# pecl_pulse_driver.net
KiCad netlist of a schematic drawn in EAGLE
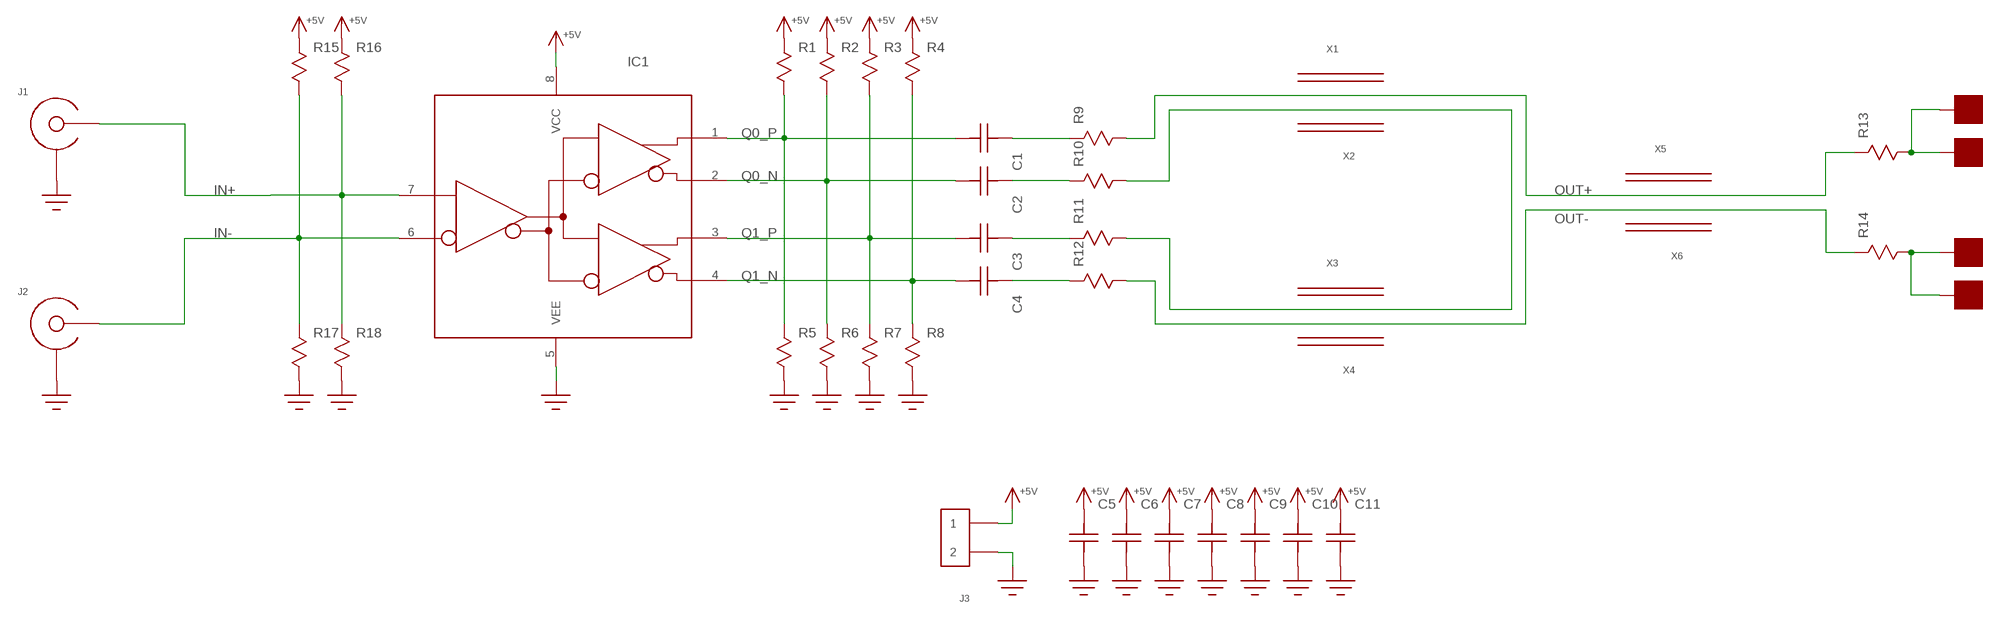
[diagram p0: schematic, sheet 1]

(export (version "E")
  (design (tool "Eeschema 10.0.6"))
  (components
    (comp (ref "C1")
      (value "C0603")
      (footprint "eagle-import:C0603")
      (libsource (lib "eagle-import") (part "C0603"))
    )
    (comp (ref "C2")
      (value "C0603")
      (footprint "eagle-import:C0603")
      (libsource (lib "eagle-import") (part "C0603"))
    )
    (comp (ref "C3")
      (value "C0603")
      (footprint "eagle-import:C0603")
      (libsource (lib "eagle-import") (part "C0603"))
    )
    (comp (ref "C4")
      (value "C0603")
      (footprint "eagle-import:C0603")
      (libsource (lib "eagle-import") (part "C0603"))
    )
    (comp (ref "C5")
      (value "C0603")
      (footprint "eagle-import:C0603")
      (libsource (lib "eagle-import") (part "C0603"))
    )
    (comp (ref "C6")
      (value "C0603")
      (footprint "eagle-import:C0603")
      (libsource (lib "eagle-import") (part "C0603"))
    )
    (comp (ref "C7")
      (value "C0805")
      (footprint "eagle-import:0805")
      (libsource (lib "eagle-import") (part "C0805"))
    )
    (comp (ref "C8")
      (value "C0603")
      (footprint "eagle-import:C0603")
      (libsource (lib "eagle-import") (part "C0603"))
    )
    (comp (ref "C9")
      (value "C0603")
      (footprint "eagle-import:C0603")
      (libsource (lib "eagle-import") (part "C0603"))
    )
    (comp (ref "C10")
      (value "C0603")
      (footprint "eagle-import:C0603")
      (libsource (lib "eagle-import") (part "C0603"))
    )
    (comp (ref "C11")
      (value "C0603")
      (footprint "eagle-import:C0603")
      (libsource (lib "eagle-import") (part "C0603"))
    )
    (comp (ref "IC1")
      (value "SY10EP89V")
      (footprint "eagle-import:SOIC8")
      (libsource (lib "eagle-import") (part "SY10EP89V"))
    )
    (comp (ref "J1")
      (value "EDGE_LAUNCH_JACK")
      (footprint "eagle-import:EDGE_LAUNCH_RF_CON")
      (libsource (lib "eagle-import") (part "EDGE_LAUNCH_JACK"))
    )
    (comp (ref "J2")
      (value "EDGE_LAUNCH_JACK")
      (footprint "eagle-import:EDGE_LAUNCH_RF_CON")
      (libsource (lib "eagle-import") (part "EDGE_LAUNCH_JACK"))
    )
    (comp (ref "J3")
      (value "HEADER_2PIN")
      (footprint "eagle-import:HEADER_2PIN")
      (libsource (lib "eagle-import") (part "HEADER_2PIN"))
    )
    (comp (ref "R1")
      (value "R0603")
      (footprint "eagle-import:R0603")
      (libsource (lib "eagle-import") (part "R0603"))
    )
    (comp (ref "R2")
      (value "R0603")
      (footprint "eagle-import:R0603")
      (libsource (lib "eagle-import") (part "R0603"))
    )
    (comp (ref "R3")
      (value "R0603")
      (footprint "eagle-import:R0603")
      (libsource (lib "eagle-import") (part "R0603"))
    )
    (comp (ref "R4")
      (value "R0603")
      (footprint "eagle-import:R0603")
      (libsource (lib "eagle-import") (part "R0603"))
    )
    (comp (ref "R5")
      (value "R0603")
      (footprint "eagle-import:R0603")
      (libsource (lib "eagle-import") (part "R0603"))
    )
    (comp (ref "R6")
      (value "R0603")
      (footprint "eagle-import:R0603")
      (libsource (lib "eagle-import") (part "R0603"))
    )
    (comp (ref "R7")
      (value "R0603")
      (footprint "eagle-import:R0603")
      (libsource (lib "eagle-import") (part "R0603"))
    )
    (comp (ref "R8")
      (value "R0603")
      (footprint "eagle-import:R0603")
      (libsource (lib "eagle-import") (part "R0603"))
    )
    (comp (ref "R9")
      (value "R0603")
      (footprint "eagle-import:R0603")
      (libsource (lib "eagle-import") (part "R0603"))
    )
    (comp (ref "R10")
      (value "R0603")
      (footprint "eagle-import:R0603")
      (libsource (lib "eagle-import") (part "R0603"))
    )
    (comp (ref "R11")
      (value "R0603")
      (footprint "eagle-import:R0603")
      (libsource (lib "eagle-import") (part "R0603"))
    )
    (comp (ref "R12")
      (value "R0603")
      (footprint "eagle-import:R0603")
      (libsource (lib "eagle-import") (part "R0603"))
    )
    (comp (ref "R13")
      (value "R0603")
      (footprint "eagle-import:R0603")
      (libsource (lib "eagle-import") (part "R0603"))
    )
    (comp (ref "R14")
      (value "R0603")
      (footprint "eagle-import:R0603")
      (libsource (lib "eagle-import") (part "R0603"))
    )
    (comp (ref "R15")
      (value "R0603")
      (footprint "eagle-import:R0603")
      (libsource (lib "eagle-import") (part "R0603"))
    )
    (comp (ref "R16")
      (value "R0603")
      (footprint "eagle-import:R0603")
      (libsource (lib "eagle-import") (part "R0603"))
    )
    (comp (ref "R17")
      (value "R0603")
      (footprint "eagle-import:R0603")
      (libsource (lib "eagle-import") (part "R0603"))
    )
    (comp (ref "R18")
      (value "R0603")
      (footprint "eagle-import:R0603")
      (libsource (lib "eagle-import") (part "R0603"))
    )
    (comp (ref "U$4")
      (value "PAD50MIL")
      (footprint "eagle-import:PAD_50MIL")
      (libsource (lib "eagle-import") (part "PAD50MIL"))
    )
    (comp (ref "U$5")
      (value "PAD50MIL")
      (footprint "eagle-import:PAD_50MIL")
      (libsource (lib "eagle-import") (part "PAD50MIL"))
    )
    (comp (ref "U$35")
      (value "PAD50MIL")
      (footprint "eagle-import:PAD_50MIL")
      (libsource (lib "eagle-import") (part "PAD50MIL"))
    )
    (comp (ref "U$36")
      (value "PAD50MIL")
      (footprint "eagle-import:PAD_50MIL")
      (libsource (lib "eagle-import") (part "PAD50MIL"))
    )
    (comp (ref "X1")
      (value "FERRITE_PLATE")
      (footprint "eagle-import:FERRITE-MP0350")
      (libsource (lib "eagle-import") (part "FERRITE_PLATE"))
    )
    (comp (ref "X2")
      (value "FERRITE_PLATE")
      (footprint "eagle-import:FERRITE-MP0350")
      (libsource (lib "eagle-import") (part "FERRITE_PLATE"))
    )
    (comp (ref "X3")
      (value "FERRITE_PLATE")
      (footprint "eagle-import:FERRITE-MP0350")
      (libsource (lib "eagle-import") (part "FERRITE_PLATE"))
    )
    (comp (ref "X4")
      (value "FERRITE_PLATE")
      (footprint "eagle-import:FERRITE-MP0350")
      (libsource (lib "eagle-import") (part "FERRITE_PLATE"))
    )
    (comp (ref "X5")
      (value "FERRITE_PLATE")
      (footprint "eagle-import:FERRITE-MP0350")
      (libsource (lib "eagle-import") (part "FERRITE_PLATE"))
    )
    (comp (ref "X6")
      (value "FERRITE_PLATE")
      (footprint "eagle-import:FERRITE-MP0350")
      (libsource (lib "eagle-import") (part "FERRITE_PLATE"))
    )
  )
  (nets
    (net (code "1") (name "+5V") (class "Default")
      (node (ref "C10") (pin "P$2") (pinfunction "P$2_P$2") (pintype "bidirectional"))
      (node (ref "C11") (pin "P$2") (pinfunction "P$2_P$2") (pintype "bidirectional"))
      (node (ref "C5") (pin "P$2") (pinfunction "P$2_P$2") (pintype "bidirectional"))
      (node (ref "C6") (pin "P$2") (pinfunction "P$2_P$2") (pintype "bidirectional"))
      (node (ref "C7") (pin "P$2") (pinfunction "P$2_P$2") (pintype "bidirectional"))
      (node (ref "C8") (pin "P$2") (pinfunction "P$2_P$2") (pintype "bidirectional"))
      (node (ref "C9") (pin "P$2") (pinfunction "P$2_P$2") (pintype "bidirectional"))
      (node (ref "IC1") (pin "8") (pinfunction "VCC_8") (pintype "bidirectional"))
      (node (ref "J3") (pin "1") (pinfunction "1_1") (pintype "bidirectional"))
      (node (ref "R1") (pin "P$1") (pinfunction "P$3_P$1") (pintype "bidirectional"))
      (node (ref "R15") (pin "P$1") (pinfunction "P$3_P$1") (pintype "bidirectional"))
      (node (ref "R16") (pin "P$1") (pinfunction "P$3_P$1") (pintype "bidirectional"))
      (node (ref "R2") (pin "P$1") (pinfunction "P$3_P$1") (pintype "bidirectional"))
      (node (ref "R3") (pin "P$1") (pinfunction "P$3_P$1") (pintype "bidirectional"))
      (node (ref "R4") (pin "P$1") (pinfunction "P$3_P$1") (pintype "bidirectional"))
    )
    (net (code "2") (name "/IN+") (class "Default")
      (node (ref "IC1") (pin "7") (pinfunction "D_7") (pintype "bidirectional"))
      (node (ref "J1") (pin "CENTER") (pinfunction "CENTER_CENTER") (pintype "bidirectional"))
      (node (ref "R16") (pin "P$2") (pinfunction "P$4_P$2") (pintype "bidirectional"))
      (node (ref "R18") (pin "P$1") (pinfunction "P$3_P$1") (pintype "bidirectional"))
    )
    (net (code "3") (name "/IN-") (class "Default")
      (node (ref "IC1") (pin "6") (pinfunction "~{D}_6") (pintype "bidirectional"))
      (node (ref "J2") (pin "CENTER") (pinfunction "CENTER_CENTER") (pintype "bidirectional"))
      (node (ref "R15") (pin "P$2") (pinfunction "P$4_P$2") (pintype "bidirectional"))
      (node (ref "R17") (pin "P$1") (pinfunction "P$3_P$1") (pintype "bidirectional"))
    )
    (net (code "4") (name "/OUT+") (class "Default")
      (node (ref "R13") (pin "P$1") (pinfunction "P$3_P$1") (pintype "bidirectional"))
      (node (ref "R9") (pin "P$2") (pinfunction "P$4_P$2") (pintype "bidirectional"))
    )
    (net (code "5") (name "/OUT-") (class "Default")
      (node (ref "R12") (pin "P$2") (pinfunction "P$4_P$2") (pintype "bidirectional"))
      (node (ref "R14") (pin "P$1") (pinfunction "P$3_P$1") (pintype "bidirectional"))
    )
    (net (code "6") (name "/Q0_N") (class "Default")
      (node (ref "C2") (pin "P$1") (pinfunction "P$1_P$1") (pintype "bidirectional"))
      (node (ref "IC1") (pin "2") (pinfunction "~{Q0}_2") (pintype "bidirectional"))
      (node (ref "R2") (pin "P$2") (pinfunction "P$4_P$2") (pintype "bidirectional"))
      (node (ref "R6") (pin "P$1") (pinfunction "P$3_P$1") (pintype "bidirectional"))
    )
    (net (code "7") (name "/Q0_P") (class "Default")
      (node (ref "C1") (pin "P$1") (pinfunction "P$1_P$1") (pintype "bidirectional"))
      (node (ref "IC1") (pin "1") (pinfunction "Q0_1") (pintype "bidirectional"))
      (node (ref "R1") (pin "P$2") (pinfunction "P$4_P$2") (pintype "bidirectional"))
      (node (ref "R5") (pin "P$1") (pinfunction "P$3_P$1") (pintype "bidirectional"))
    )
    (net (code "8") (name "/Q1_N") (class "Default")
      (node (ref "C4") (pin "P$1") (pinfunction "P$1_P$1") (pintype "bidirectional"))
      (node (ref "IC1") (pin "4") (pinfunction "~{Q1}_4") (pintype "bidirectional"))
      (node (ref "R4") (pin "P$2") (pinfunction "P$4_P$2") (pintype "bidirectional"))
      (node (ref "R8") (pin "P$1") (pinfunction "P$3_P$1") (pintype "bidirectional"))
    )
    (net (code "9") (name "/Q1_P") (class "Default")
      (node (ref "C3") (pin "P$1") (pinfunction "P$1_P$1") (pintype "bidirectional"))
      (node (ref "IC1") (pin "3") (pinfunction "Q1_3") (pintype "bidirectional"))
      (node (ref "R3") (pin "P$2") (pinfunction "P$4_P$2") (pintype "bidirectional"))
      (node (ref "R7") (pin "P$1") (pinfunction "P$3_P$1") (pintype "bidirectional"))
    )
    (net (code "10") (name "GND") (class "Default")
      (node (ref "C10") (pin "P$1") (pinfunction "P$1_P$1") (pintype "bidirectional"))
      (node (ref "C11") (pin "P$1") (pinfunction "P$1_P$1") (pintype "bidirectional"))
      (node (ref "C5") (pin "P$1") (pinfunction "P$1_P$1") (pintype "bidirectional"))
      (node (ref "C6") (pin "P$1") (pinfunction "P$1_P$1") (pintype "bidirectional"))
      (node (ref "C7") (pin "P$1") (pinfunction "P$1_P$1") (pintype "bidirectional"))
      (node (ref "C8") (pin "P$1") (pinfunction "P$1_P$1") (pintype "bidirectional"))
      (node (ref "C9") (pin "P$1") (pinfunction "P$1_P$1") (pintype "bidirectional"))
      (node (ref "IC1") (pin "5") (pinfunction "VEE_5") (pintype "bidirectional"))
      (node (ref "J1") (pin "GND@1") (pinfunction "SHIELD_GND@1") (pintype "bidirectional"))
      (node (ref "J1") (pin "GND@10") (pinfunction "SHIELD_GND@10") (pintype "bidirectional"))
      (node (ref "J1") (pin "GND@11") (pinfunction "SHIELD_GND@11") (pintype "bidirectional"))
      (node (ref "J1") (pin "GND@12") (pinfunction "SHIELD_GND@12") (pintype "bidirectional"))
      (node (ref "J1") (pin "GND@2") (pinfunction "SHIELD_GND@2") (pintype "bidirectional"))
      (node (ref "J1") (pin "GND@3") (pinfunction "SHIELD_GND@3") (pintype "bidirectional"))
      (node (ref "J1") (pin "GND@4") (pinfunction "SHIELD_GND@4") (pintype "bidirectional"))
      (node (ref "J1") (pin "GND@5") (pinfunction "SHIELD_GND@5") (pintype "bidirectional"))
      (node (ref "J1") (pin "GND@6") (pinfunction "SHIELD_GND@6") (pintype "bidirectional"))
      (node (ref "J1") (pin "GND@7") (pinfunction "SHIELD_GND@7") (pintype "bidirectional"))
      (node (ref "J1") (pin "GND@8") (pinfunction "SHIELD_GND@8") (pintype "bidirectional"))
      (node (ref "J1") (pin "GND@9") (pinfunction "SHIELD_GND@9") (pintype "bidirectional"))
      (node (ref "J1") (pin "SHIELD@1") (pinfunction "SHIELD_SHIELD@1") (pintype "bidirectional"))
      (node (ref "J1") (pin "SHIELD@2") (pinfunction "SHIELD_SHIELD@2") (pintype "bidirectional"))
      (node (ref "J2") (pin "GND@1") (pinfunction "SHIELD_GND@1") (pintype "bidirectional"))
      (node (ref "J2") (pin "GND@10") (pinfunction "SHIELD_GND@10") (pintype "bidirectional"))
      (node (ref "J2") (pin "GND@11") (pinfunction "SHIELD_GND@11") (pintype "bidirectional"))
      (node (ref "J2") (pin "GND@12") (pinfunction "SHIELD_GND@12") (pintype "bidirectional"))
      (node (ref "J2") (pin "GND@2") (pinfunction "SHIELD_GND@2") (pintype "bidirectional"))
      (node (ref "J2") (pin "GND@3") (pinfunction "SHIELD_GND@3") (pintype "bidirectional"))
      (node (ref "J2") (pin "GND@4") (pinfunction "SHIELD_GND@4") (pintype "bidirectional"))
      (node (ref "J2") (pin "GND@5") (pinfunction "SHIELD_GND@5") (pintype "bidirectional"))
      (node (ref "J2") (pin "GND@6") (pinfunction "SHIELD_GND@6") (pintype "bidirectional"))
      (node (ref "J2") (pin "GND@7") (pinfunction "SHIELD_GND@7") (pintype "bidirectional"))
      (node (ref "J2") (pin "GND@8") (pinfunction "SHIELD_GND@8") (pintype "bidirectional"))
      (node (ref "J2") (pin "GND@9") (pinfunction "SHIELD_GND@9") (pintype "bidirectional"))
      (node (ref "J2") (pin "SHIELD@1") (pinfunction "SHIELD_SHIELD@1") (pintype "bidirectional"))
      (node (ref "J2") (pin "SHIELD@2") (pinfunction "SHIELD_SHIELD@2") (pintype "bidirectional"))
      (node (ref "J3") (pin "2") (pinfunction "2_2") (pintype "bidirectional"))
      (node (ref "R17") (pin "P$2") (pinfunction "P$4_P$2") (pintype "bidirectional"))
      (node (ref "R18") (pin "P$2") (pinfunction "P$4_P$2") (pintype "bidirectional"))
      (node (ref "R5") (pin "P$2") (pinfunction "P$4_P$2") (pintype "bidirectional"))
      (node (ref "R6") (pin "P$2") (pinfunction "P$4_P$2") (pintype "bidirectional"))
      (node (ref "R7") (pin "P$2") (pinfunction "P$4_P$2") (pintype "bidirectional"))
      (node (ref "R8") (pin "P$2") (pinfunction "P$4_P$2") (pintype "bidirectional"))
    )
    (net (code "11") (name "Net-(R9-P$3)") (class "Default")
      (node (ref "C1") (pin "P$2") (pinfunction "P$2_P$2") (pintype "bidirectional"))
      (node (ref "R9") (pin "P$1") (pinfunction "P$3_P$1") (pintype "bidirectional"))
    )
    (net (code "12") (name "Net-(R10-P$3)") (class "Default")
      (node (ref "C2") (pin "P$2") (pinfunction "P$2_P$2") (pintype "bidirectional"))
      (node (ref "R10") (pin "P$1") (pinfunction "P$3_P$1") (pintype "bidirectional"))
    )
    (net (code "13") (name "Net-(R10-P$4)") (class "Default")
      (node (ref "R10") (pin "P$2") (pinfunction "P$4_P$2") (pintype "bidirectional"))
      (node (ref "R11") (pin "P$2") (pinfunction "P$4_P$2") (pintype "bidirectional"))
    )
    (net (code "14") (name "Net-(R11-P$3)") (class "Default")
      (node (ref "C3") (pin "P$2") (pinfunction "P$2_P$2") (pintype "bidirectional"))
      (node (ref "R11") (pin "P$1") (pinfunction "P$3_P$1") (pintype "bidirectional"))
    )
    (net (code "15") (name "Net-(R12-P$3)") (class "Default")
      (node (ref "C4") (pin "P$2") (pinfunction "P$2_P$2") (pintype "bidirectional"))
      (node (ref "R12") (pin "P$1") (pinfunction "P$3_P$1") (pintype "bidirectional"))
    )
    (net (code "16") (name "Net-(R13-P$4)") (class "Default")
      (node (ref "R13") (pin "P$2") (pinfunction "P$4_P$2") (pintype "bidirectional"))
      (node (ref "U$35") (pin "P$1") (pinfunction "P$1_P$1") (pintype "bidirectional"))
      (node (ref "U$4") (pin "P$1") (pinfunction "P$1_P$1") (pintype "bidirectional"))
    )
    (net (code "17") (name "Net-(R14-P$4)") (class "Default")
      (node (ref "R14") (pin "P$2") (pinfunction "P$4_P$2") (pintype "bidirectional"))
      (node (ref "U$36") (pin "P$1") (pinfunction "P$1_P$1") (pintype "bidirectional"))
      (node (ref "U$5") (pin "P$1") (pinfunction "P$1_P$1") (pintype "bidirectional"))
    )
  )
)
